# bic_sheild_draft1.net
KiCad netlist of a schematic drawn in EAGLE
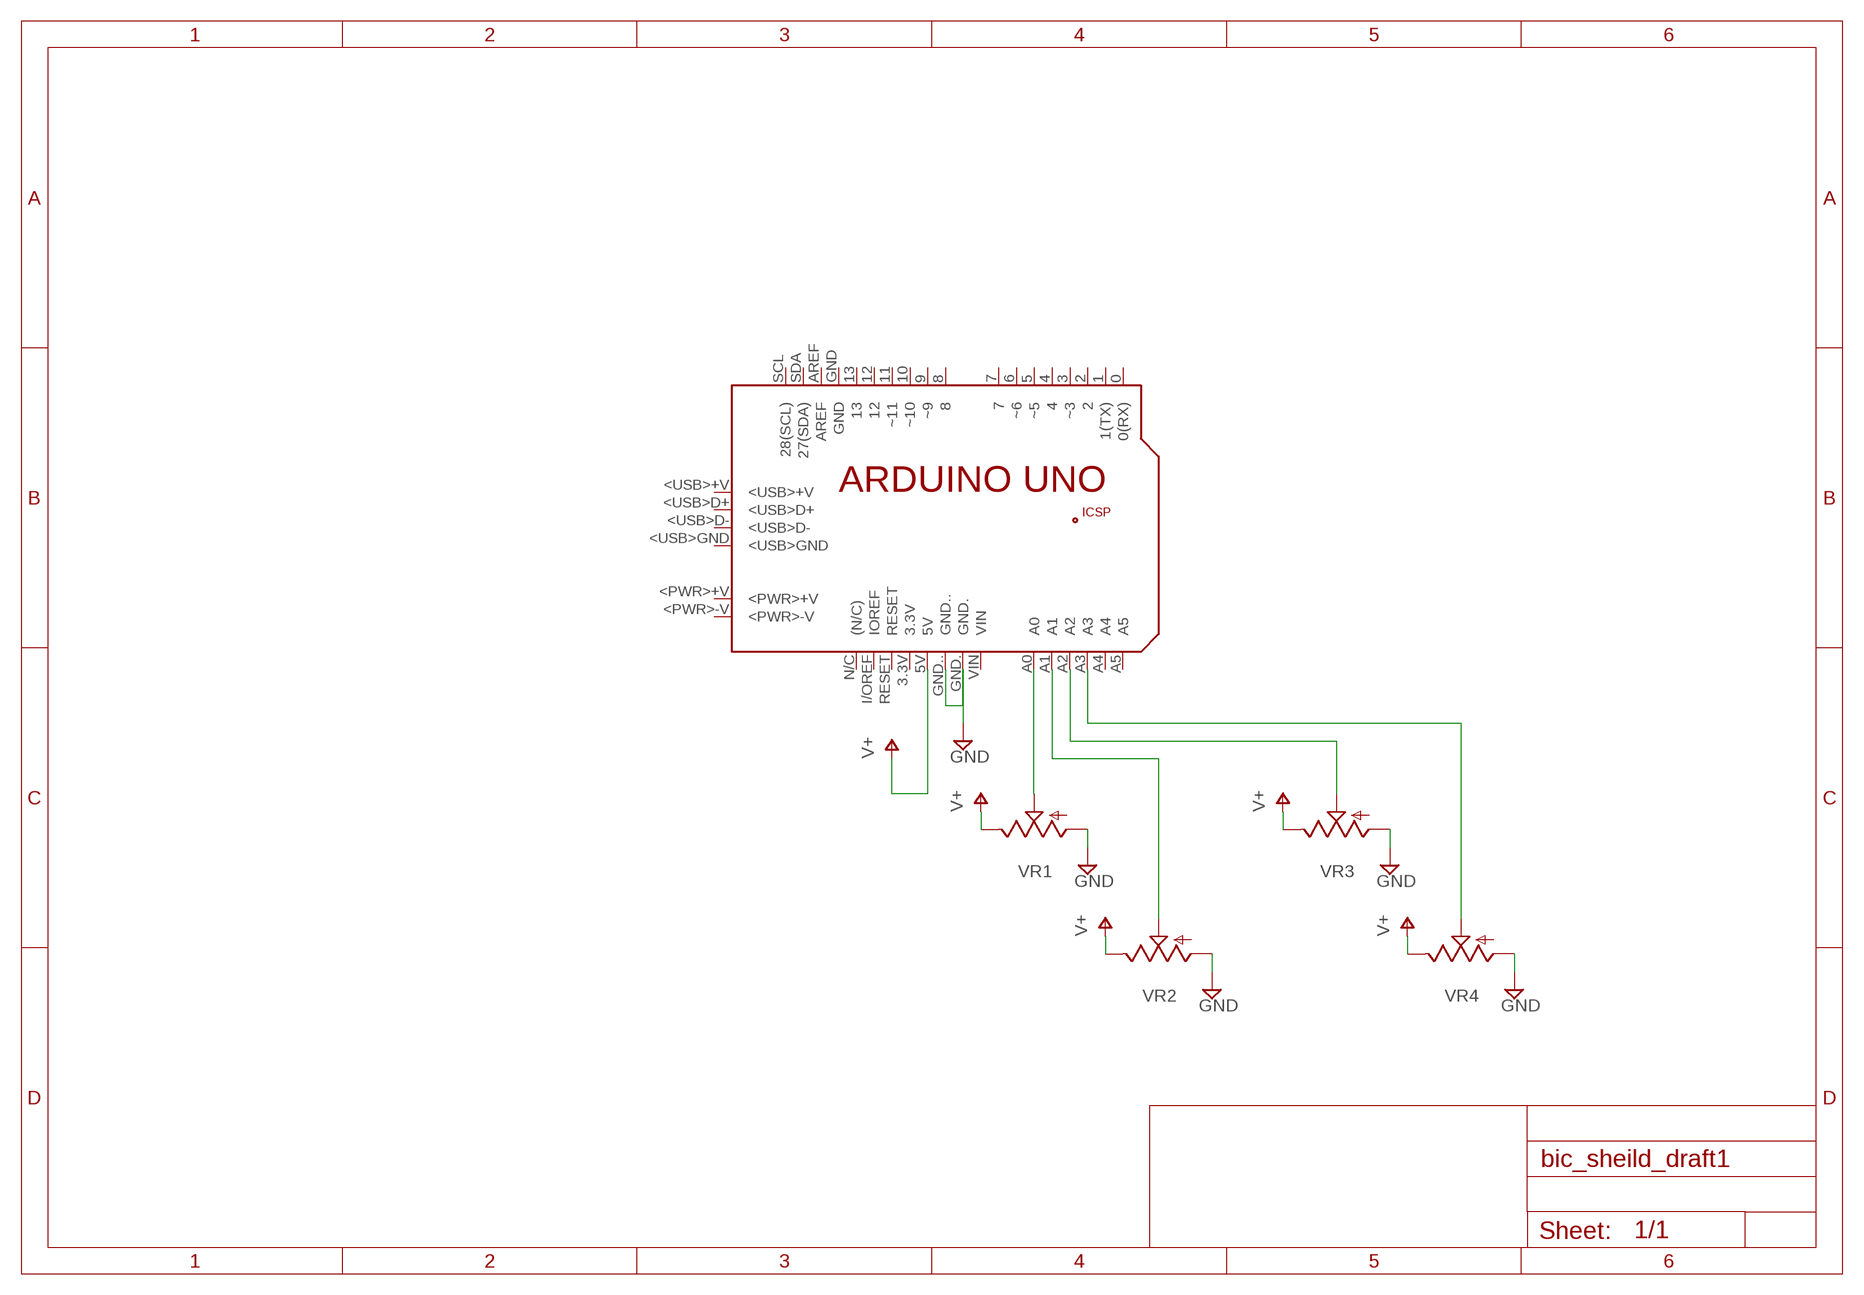
[diagram p0: schematic, sheet 1]

(export (version "E")
  (design (tool "Eeschema 10.0.6"))
  (components
    (comp (ref "PCB1")
      (value "ARDUINO_UNO")
      (footprint "eagle-import:ARDUINO_UNO")
      (libsource (lib "eagle-import") (part "ARDUINO_UNO"))
    )
    (comp (ref "VR1")
      (value "9MM_SNAP-IN_POT_")
      (footprint "eagle-import:9MM_SNAP-IN_POT")
      (libsource (lib "eagle-import") (part "9MM_SNAP-IN_POT_"))
    )
    (comp (ref "VR2")
      (value "9MM_SNAP-IN_POT_")
      (footprint "eagle-import:9MM_SNAP-IN_POT")
      (libsource (lib "eagle-import") (part "9MM_SNAP-IN_POT_"))
    )
    (comp (ref "VR3")
      (value "9MM_SNAP-IN_POT_")
      (footprint "eagle-import:9MM_SNAP-IN_POT")
      (libsource (lib "eagle-import") (part "9MM_SNAP-IN_POT_"))
    )
    (comp (ref "VR4")
      (value "9MM_SNAP-IN_POT_")
      (footprint "eagle-import:9MM_SNAP-IN_POT")
      (libsource (lib "eagle-import") (part "9MM_SNAP-IN_POT_"))
    )
  )
  (nets
    (net (code "1") (name "GND") (class "Default")
      (node (ref "PCB1") (pin "GND.") (pinfunction "GND._GND.") (pintype "bidirectional"))
      (node (ref "PCB1") (pin "GND..") (pinfunction "GND.._GND..") (pintype "bidirectional"))
      (node (ref "VR1") (pin "1") (pinfunction "A_1") (pintype "passive"))
      (node (ref "VR2") (pin "1") (pinfunction "A_1") (pintype "passive"))
      (node (ref "VR3") (pin "1") (pinfunction "A_1") (pintype "passive"))
      (node (ref "VR4") (pin "1") (pinfunction "A_1") (pintype "passive"))
    )
    (net (code "2") (name "Net-(VR1-S)") (class "Default")
      (node (ref "PCB1") (pin "A0") (pinfunction "A0_A0") (pintype "bidirectional"))
      (node (ref "VR1") (pin "2") (pinfunction "S_2") (pintype "passive"))
    )
    (net (code "3") (name "Net-(VR2-S)") (class "Default")
      (node (ref "PCB1") (pin "A1") (pinfunction "A1_A1") (pintype "bidirectional"))
      (node (ref "VR2") (pin "2") (pinfunction "S_2") (pintype "passive"))
    )
    (net (code "4") (name "Net-(VR3-S)") (class "Default")
      (node (ref "PCB1") (pin "A2") (pinfunction "A2_A2") (pintype "bidirectional"))
      (node (ref "VR3") (pin "2") (pinfunction "S_2") (pintype "passive"))
    )
    (net (code "5") (name "Net-(VR4-S)") (class "Default")
      (node (ref "PCB1") (pin "A3") (pinfunction "A3_A3") (pintype "bidirectional"))
      (node (ref "VR4") (pin "2") (pinfunction "S_2") (pintype "passive"))
    )
    (net (code "6") (name "V+") (class "Default")
      (node (ref "PCB1") (pin "5V") (pinfunction "5V_5V") (pintype "bidirectional"))
      (node (ref "VR1") (pin "3") (pinfunction "E_3") (pintype "passive"))
      (node (ref "VR2") (pin "3") (pinfunction "E_3") (pintype "passive"))
      (node (ref "VR3") (pin "3") (pinfunction "E_3") (pintype "passive"))
      (node (ref "VR4") (pin "3") (pinfunction "E_3") (pintype "passive"))
    )
    (net (code "7") (name "unconnected-(PCB1-(N{slash}C)-PadN{slash}C)") (class "Default")
      (node (ref "PCB1") (pin "N/C") (pinfunction "(N/C)_N/C") (pintype "bidirectional"))
    )
    (net (code "8") (name "unconnected-(PCB1-0(RX)-Pad0)") (class "Default")
      (node (ref "PCB1") (pin "0") (pinfunction "0(RX)_0") (pintype "bidirectional"))
    )
    (net (code "9") (name "unconnected-(PCB1-1(TX)-Pad1)") (class "Default")
      (node (ref "PCB1") (pin "1") (pinfunction "1(TX)_1") (pintype "bidirectional"))
    )
    (net (code "10") (name "unconnected-(PCB1-27(SDA)-PadSDA)") (class "Default")
      (node (ref "PCB1") (pin "SDA") (pinfunction "27(SDA)_SDA") (pintype "bidirectional"))
    )
    (net (code "11") (name "unconnected-(PCB1-28(SCL)-PadSCL)") (class "Default")
      (node (ref "PCB1") (pin "SCL") (pinfunction "28(SCL)_SCL") (pintype "bidirectional"))
    )
    (net (code "12") (name "unconnected-(PCB1-IOREF-PadI{slash}OREF)") (class "Default")
      (node (ref "PCB1") (pin "I/OREF") (pinfunction "IOREF_I/OREF") (pintype "bidirectional"))
    )
    (net (code "13") (name "unconnected-(PCB1-Pad+5V)") (class "Default")
      (node (ref "PCB1") (pin "+5V") (pinfunction "+5V_+5V") (pintype "bidirectional"))
    )
    (net (code "14") (name "unconnected-(PCB1-Pad2)") (class "Default")
      (node (ref "PCB1") (pin "2") (pinfunction "2_2") (pintype "bidirectional"))
    )
    (net (code "15") (name "unconnected-(PCB1-Pad3.3V)") (class "Default")
      (node (ref "PCB1") (pin "3.3V") (pinfunction "3.3V_3.3V") (pintype "bidirectional"))
    )
    (net (code "16") (name "unconnected-(PCB1-Pad4)") (class "Default")
      (node (ref "PCB1") (pin "4") (pinfunction "4_4") (pintype "bidirectional"))
    )
    (net (code "17") (name "unconnected-(PCB1-Pad7)") (class "Default")
      (node (ref "PCB1") (pin "7") (pinfunction "7_7") (pintype "bidirectional"))
    )
    (net (code "18") (name "unconnected-(PCB1-Pad8)") (class "Default")
      (node (ref "PCB1") (pin "8") (pinfunction "8_8") (pintype "bidirectional"))
    )
    (net (code "19") (name "unconnected-(PCB1-Pad12)") (class "Default")
      (node (ref "PCB1") (pin "12") (pinfunction "12_12") (pintype "bidirectional"))
    )
    (net (code "20") (name "unconnected-(PCB1-Pad13)") (class "Default")
      (node (ref "PCB1") (pin "13") (pinfunction "13_13") (pintype "bidirectional"))
    )
    (net (code "21") (name "unconnected-(PCB1-Pad<PWR>+V)") (class "Default")
      (node (ref "PCB1") (pin "<PWR>+V") (pinfunction "<PWR>+V_<PWR>+V") (pintype "bidirectional"))
    )
    (net (code "22") (name "unconnected-(PCB1-Pad<PWR>-V)") (class "Default")
      (node (ref "PCB1") (pin "<PWR>-V") (pinfunction "<PWR>-V_<PWR>-V") (pintype "bidirectional"))
    )
    (net (code "23") (name "unconnected-(PCB1-Pad<USB>+V)") (class "Default")
      (node (ref "PCB1") (pin "<USB>+V") (pinfunction "<USB>+V_<USB>+V") (pintype "bidirectional"))
    )
    (net (code "24") (name "unconnected-(PCB1-Pad<USB>D+)") (class "Default")
      (node (ref "PCB1") (pin "<USB>D+") (pinfunction "<USB>D+_<USB>D+") (pintype "bidirectional"))
    )
    (net (code "25") (name "unconnected-(PCB1-Pad<USB>D-)") (class "Default")
      (node (ref "PCB1") (pin "<USB>D-") (pinfunction "<USB>D-_<USB>D-") (pintype "bidirectional"))
    )
    (net (code "26") (name "unconnected-(PCB1-Pad<USB>GND)") (class "Default")
      (node (ref "PCB1") (pin "<USB>GND") (pinfunction "<USB>GND_<USB>GND") (pintype "bidirectional"))
    )
    (net (code "27") (name "unconnected-(PCB1-PadA4)") (class "Default")
      (node (ref "PCB1") (pin "A4") (pinfunction "A4_A4") (pintype "bidirectional"))
    )
    (net (code "28") (name "unconnected-(PCB1-PadA5)") (class "Default")
      (node (ref "PCB1") (pin "A5") (pinfunction "A5_A5") (pintype "bidirectional"))
    )
    (net (code "29") (name "unconnected-(PCB1-PadAREF)") (class "Default")
      (node (ref "PCB1") (pin "AREF") (pinfunction "AREF_AREF") (pintype "bidirectional"))
    )
    (net (code "30") (name "unconnected-(PCB1-PadGND)") (class "Default")
      (node (ref "PCB1") (pin "GND") (pinfunction "GND_GND") (pintype "bidirectional"))
    )
    (net (code "31") (name "unconnected-(PCB1-PadGND_)") (class "Default")
      (node (ref "PCB1") (pin "GND_") (pinfunction "GND__GND_") (pintype "bidirectional"))
    )
    (net (code "32") (name "unconnected-(PCB1-PadMISO)") (class "Default")
      (node (ref "PCB1") (pin "MISO") (pinfunction "MISO_MISO") (pintype "bidirectional"))
    )
    (net (code "33") (name "unconnected-(PCB1-PadMOSI)") (class "Default")
      (node (ref "PCB1") (pin "MOSI") (pinfunction "MOSI_MOSI") (pintype "bidirectional"))
    )
    (net (code "34") (name "unconnected-(PCB1-PadRESET)") (class "Default")
      (node (ref "PCB1") (pin "RESET") (pinfunction "RESET_RESET") (pintype "bidirectional"))
    )
    (net (code "35") (name "unconnected-(PCB1-PadRESET.)") (class "Default")
      (node (ref "PCB1") (pin "RESET.") (pinfunction "RESET._RESET.") (pintype "bidirectional"))
    )
    (net (code "36") (name "unconnected-(PCB1-PadSCK)") (class "Default")
      (node (ref "PCB1") (pin "SCK") (pinfunction "SCK_SCK") (pintype "bidirectional"))
    )
    (net (code "37") (name "unconnected-(PCB1-PadVIN)") (class "Default")
      (node (ref "PCB1") (pin "VIN") (pinfunction "VIN_VIN") (pintype "bidirectional"))
    )
    (net (code "38") (name "unconnected-(PCB1-~{3}-Pad3)") (class "Default")
      (node (ref "PCB1") (pin "3") (pinfunction "~{3}_3") (pintype "bidirectional"))
    )
    (net (code "39") (name "unconnected-(PCB1-~{5}-Pad5)") (class "Default")
      (node (ref "PCB1") (pin "5") (pinfunction "~{5}_5") (pintype "bidirectional"))
    )
    (net (code "40") (name "unconnected-(PCB1-~{6}-Pad6)") (class "Default")
      (node (ref "PCB1") (pin "6") (pinfunction "~{6}_6") (pintype "bidirectional"))
    )
    (net (code "41") (name "unconnected-(PCB1-~{9}-Pad9)") (class "Default")
      (node (ref "PCB1") (pin "9") (pinfunction "~{9}_9") (pintype "bidirectional"))
    )
    (net (code "42") (name "unconnected-(PCB1-~{10}-Pad10)") (class "Default")
      (node (ref "PCB1") (pin "10") (pinfunction "~{10}_10") (pintype "bidirectional"))
    )
    (net (code "43") (name "unconnected-(PCB1-~{11}-Pad11)") (class "Default")
      (node (ref "PCB1") (pin "11") (pinfunction "~{11}_11") (pintype "bidirectional"))
    )
  )
)
